# stamp_module.net
KiCad netlist of a schematic drawn in EAGLE
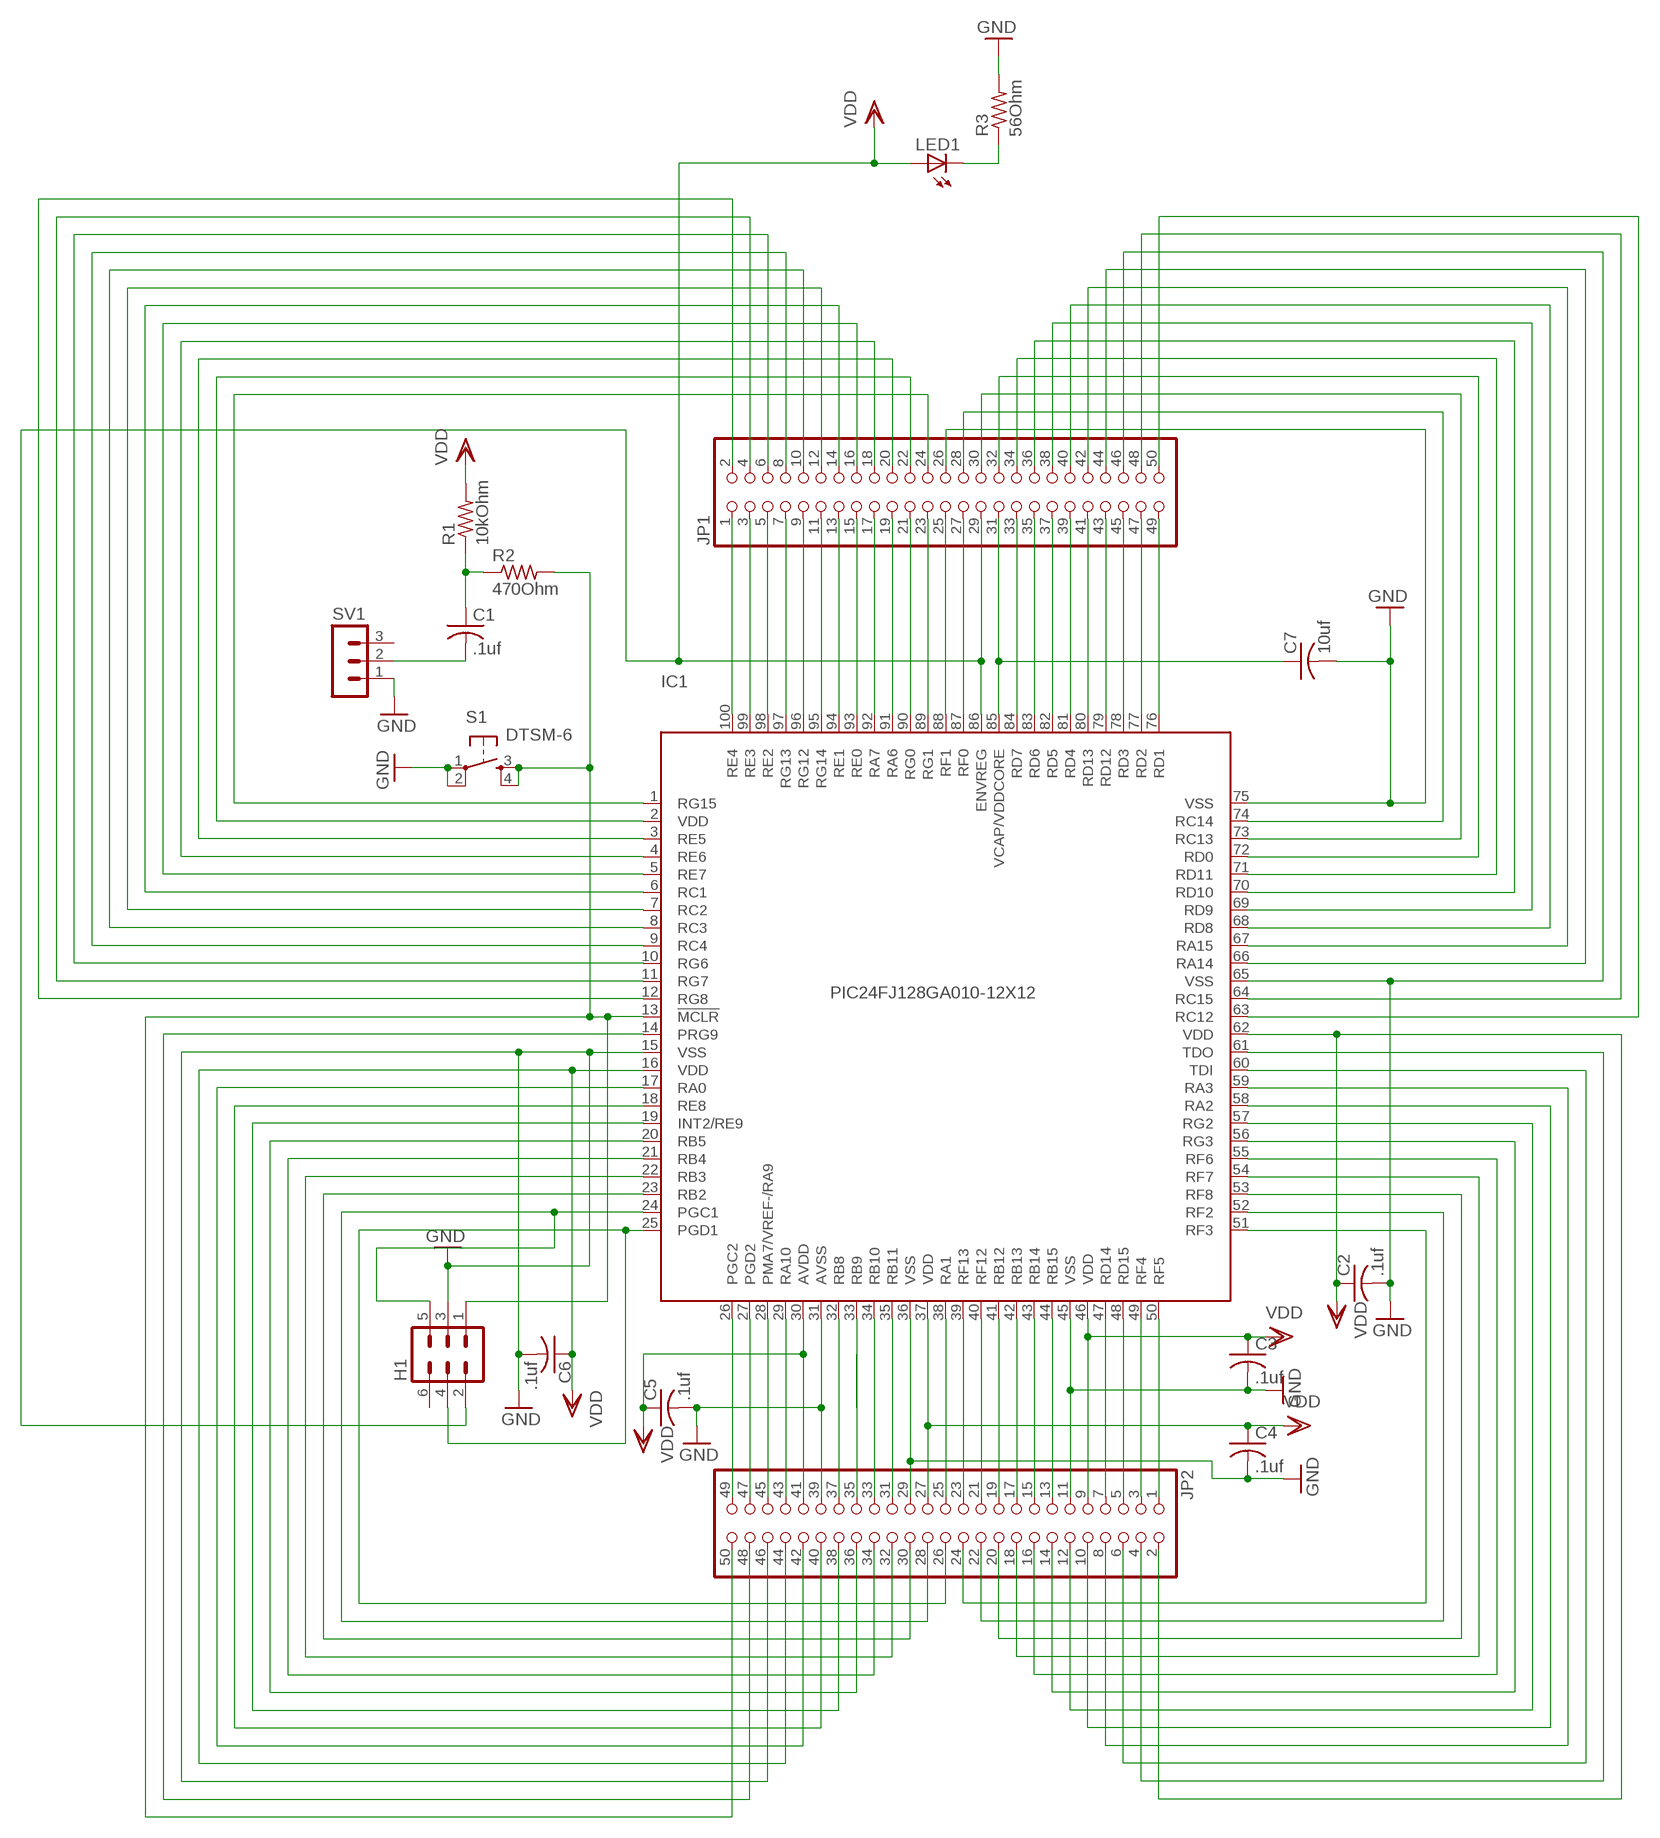
[diagram p0: schematic, sheet 1]

(export (version "E")
  (design (tool "Eeschema 10.0.6"))
  (components
    (comp (ref "C1")
      (value ".1uf")
      (footprint "eagle-import:C1206")
      (libsource (lib "eagle-import") (part "C-USC1206"))
    )
    (comp (ref "C2")
      (value ".1uf")
      (footprint "eagle-import:C1206")
      (libsource (lib "eagle-import") (part "C-USC1206"))
    )
    (comp (ref "C3")
      (value ".1uf")
      (footprint "eagle-import:C1206")
      (libsource (lib "eagle-import") (part "C-USC1206"))
    )
    (comp (ref "C4")
      (value ".1uf")
      (footprint "eagle-import:C1206")
      (libsource (lib "eagle-import") (part "C-USC1206"))
    )
    (comp (ref "C5")
      (value ".1uf")
      (footprint "eagle-import:C1206")
      (libsource (lib "eagle-import") (part "C-USC1206"))
    )
    (comp (ref "C6")
      (value ".1uf")
      (footprint "eagle-import:C1206")
      (libsource (lib "eagle-import") (part "C-USC1206"))
    )
    (comp (ref "C7")
      (value "10uf")
      (footprint "eagle-import:C1206")
      (libsource (lib "eagle-import") (part "C-USC1206"))
    )
    (comp (ref "H1")
      (value "MA03-2")
      (footprint "eagle-import:MA03-2")
      (libsource (lib "eagle-import") (part "MA03-2"))
    )
    (comp (ref "IC1")
      (value "PIC24FJ128GA010-12X12")
      (footprint "eagle-import:SQFP-S-12X12-100")
      (libsource (lib "eagle-import") (part "PIC24FJ128GA010-12X12"))
    )
    (comp (ref "JP1")
      (value "PINHD-2X25")
      (footprint "eagle-import:2X25")
      (libsource (lib "eagle-import") (part "PINHD-2X25"))
    )
    (comp (ref "JP2")
      (value "PINHD-2X25")
      (footprint "eagle-import:2X25")
      (libsource (lib "eagle-import") (part "PINHD-2X25"))
    )
    (comp (ref "LED1")
      (value "LEDCHIPLED_0805")
      (footprint "eagle-import:CHIPLED_0805")
      (libsource (lib "eagle-import") (part "LEDCHIPLED_0805"))
    )
    (comp (ref "R1")
      (value "10kOhm")
      (footprint "eagle-import:R1206")
      (libsource (lib "eagle-import") (part "R-US_R1206"))
    )
    (comp (ref "R2")
      (value "470Ohm")
      (footprint "eagle-import:R1206")
      (libsource (lib "eagle-import") (part "R-US_R1206"))
    )
    (comp (ref "R3")
      (value "56Ohm")
      (footprint "eagle-import:R0805")
      (libsource (lib "eagle-import") (part "R-US_R0805"))
    )
    (comp (ref "S1")
      (value "DTSM-6")
      (footprint "eagle-import:DTSM-6")
      (libsource (lib "eagle-import") (part "DTSM-6"))
    )
    (comp (ref "SV1")
      (value "MA03-1")
      (footprint "eagle-import:MA03-1")
      (libsource (lib "eagle-import") (part "MA03-1"))
    )
  )
  (nets
    (net (code "1") (name "GND") (class "Default")
      (node (ref "C2") (pin "2") (pinfunction "2_2") (pintype "passive"))
      (node (ref "C3") (pin "2") (pinfunction "2_2") (pintype "passive"))
      (node (ref "C4") (pin "2") (pinfunction "2_2") (pintype "passive"))
      (node (ref "C5") (pin "2") (pinfunction "2_2") (pintype "passive"))
      (node (ref "C6") (pin "2") (pinfunction "2_2") (pintype "passive"))
      (node (ref "C7") (pin "2") (pinfunction "2_2") (pintype "passive"))
      (node (ref "H1") (pin "3") (pinfunction "3_3") (pintype "passive"))
      (node (ref "IC1") (pin "15") (pinfunction "VSS_15") (pintype "power_in"))
      (node (ref "IC1") (pin "31") (pinfunction "AVSS_31") (pintype "power_in"))
      (node (ref "IC1") (pin "36") (pinfunction "VSS_36") (pintype "power_in"))
      (node (ref "IC1") (pin "45") (pinfunction "VSS_45") (pintype "power_in"))
      (node (ref "IC1") (pin "65") (pinfunction "VSS_65") (pintype "power_in"))
      (node (ref "IC1") (pin "75") (pinfunction "VSS_75") (pintype "power_in"))
      (node (ref "JP1") (pin "26") (pinfunction "26_26") (pintype "passive"))
      (node (ref "JP1") (pin "46") (pinfunction "46_46") (pintype "passive"))
      (node (ref "JP2") (pin "11") (pinfunction "11_11") (pintype "passive"))
      (node (ref "JP2") (pin "29") (pinfunction "29_29") (pintype "passive"))
      (node (ref "JP2") (pin "39") (pinfunction "39_39") (pintype "passive"))
      (node (ref "JP2") (pin "46") (pinfunction "46_46") (pintype "passive"))
      (node (ref "R3") (pin "2") (pinfunction "2_2") (pintype "passive"))
      (node (ref "S1") (pin "1") (pinfunction "1_1") (pintype "passive"))
      (node (ref "S1") (pin "2") (pinfunction "2_2") (pintype "passive"))
      (node (ref "SV1") (pin "1") (pinfunction "1_1") (pintype "passive"))
    )
    (net (code "2") (name "Net-(C1-Pad1)") (class "Default")
      (node (ref "C1") (pin "1") (pinfunction "1_1") (pintype "passive"))
      (node (ref "R1") (pin "1") (pinfunction "1_1") (pintype "passive"))
      (node (ref "R2") (pin "1") (pinfunction "1_1") (pintype "passive"))
    )
    (net (code "3") (name "Net-(C1-Pad2)") (class "Default")
      (node (ref "C1") (pin "2") (pinfunction "2_2") (pintype "passive"))
      (node (ref "SV1") (pin "2") (pinfunction "2_2") (pintype "passive"))
    )
    (net (code "4") (name "Net-(IC1-INT2{slash}RE9)") (class "Default")
      (node (ref "IC1") (pin "19") (pinfunction "INT2/RE9_19") (pintype "bidirectional"))
      (node (ref "JP2") (pin "38") (pinfunction "38_38") (pintype "passive"))
    )
    (net (code "5") (name "Net-(IC1-PGC1)") (class "Default")
      (node (ref "H1") (pin "5") (pinfunction "5_5") (pintype "passive"))
      (node (ref "IC1") (pin "24") (pinfunction "PGC1_24") (pintype "bidirectional"))
      (node (ref "JP2") (pin "28") (pinfunction "28_28") (pintype "passive"))
    )
    (net (code "6") (name "Net-(IC1-PGC2)") (class "Default")
      (node (ref "IC1") (pin "26") (pinfunction "PGC2_26") (pintype "bidirectional"))
      (node (ref "JP2") (pin "49") (pinfunction "49_49") (pintype "passive"))
    )
    (net (code "7") (name "Net-(IC1-PGD1)") (class "Default")
      (node (ref "H1") (pin "4") (pinfunction "4_4") (pintype "passive"))
      (node (ref "IC1") (pin "25") (pinfunction "PGD1_25") (pintype "bidirectional"))
      (node (ref "JP2") (pin "26") (pinfunction "26_26") (pintype "passive"))
    )
    (net (code "8") (name "Net-(IC1-PGD2)") (class "Default")
      (node (ref "IC1") (pin "27") (pinfunction "PGD2_27") (pintype "bidirectional"))
      (node (ref "JP2") (pin "47") (pinfunction "47_47") (pintype "passive"))
    )
    (net (code "9") (name "Net-(IC1-PMA7{slash}VREF-{slash}RA9)") (class "Default")
      (node (ref "IC1") (pin "28") (pinfunction "PMA7/VREF-/RA9_28") (pintype "bidirectional"))
      (node (ref "JP2") (pin "45") (pinfunction "45_45") (pintype "passive"))
    )
    (net (code "10") (name "Net-(IC1-PRG9)") (class "Default")
      (node (ref "IC1") (pin "14") (pinfunction "PRG9_14") (pintype "bidirectional"))
      (node (ref "JP2") (pin "48") (pinfunction "48_48") (pintype "passive"))
    )
    (net (code "11") (name "Net-(IC1-RA0)") (class "Default")
      (node (ref "IC1") (pin "17") (pinfunction "RA0_17") (pintype "bidirectional"))
      (node (ref "JP2") (pin "42") (pinfunction "42_42") (pintype "passive"))
    )
    (net (code "12") (name "Net-(IC1-RA1)") (class "Default")
      (node (ref "IC1") (pin "38") (pinfunction "RA1_38") (pintype "bidirectional"))
      (node (ref "JP2") (pin "25") (pinfunction "25_25") (pintype "passive"))
    )
    (net (code "13") (name "Net-(IC1-RA2)") (class "Default")
      (node (ref "IC1") (pin "58") (pinfunction "RA2_58") (pintype "bidirectional"))
      (node (ref "JP2") (pin "10") (pinfunction "10_10") (pintype "passive"))
    )
    (net (code "14") (name "Net-(IC1-RA3)") (class "Default")
      (node (ref "IC1") (pin "59") (pinfunction "RA3_59") (pintype "bidirectional"))
      (node (ref "JP2") (pin "8") (pinfunction "8_8") (pintype "passive"))
    )
    (net (code "15") (name "Net-(IC1-RA6)") (class "Default")
      (node (ref "IC1") (pin "91") (pinfunction "RA6_91") (pintype "bidirectional"))
      (node (ref "JP1") (pin "19") (pinfunction "19_19") (pintype "passive"))
    )
    (net (code "16") (name "Net-(IC1-RA7)") (class "Default")
      (node (ref "IC1") (pin "92") (pinfunction "RA7_92") (pintype "bidirectional"))
      (node (ref "JP1") (pin "17") (pinfunction "17_17") (pintype "passive"))
    )
    (net (code "17") (name "Net-(IC1-RA10)") (class "Default")
      (node (ref "IC1") (pin "29") (pinfunction "RA10_29") (pintype "bidirectional"))
      (node (ref "JP2") (pin "43") (pinfunction "43_43") (pintype "passive"))
    )
    (net (code "18") (name "Net-(IC1-RA14)") (class "Default")
      (node (ref "IC1") (pin "66") (pinfunction "RA14_66") (pintype "bidirectional"))
      (node (ref "JP1") (pin "44") (pinfunction "44_44") (pintype "passive"))
    )
    (net (code "19") (name "Net-(IC1-RA15)") (class "Default")
      (node (ref "IC1") (pin "67") (pinfunction "RA15_67") (pintype "bidirectional"))
      (node (ref "JP1") (pin "42") (pinfunction "42_42") (pintype "passive"))
    )
    (net (code "20") (name "Net-(IC1-RB2)") (class "Default")
      (node (ref "IC1") (pin "23") (pinfunction "RB2_23") (pintype "bidirectional"))
      (node (ref "JP2") (pin "30") (pinfunction "30_30") (pintype "passive"))
    )
    (net (code "21") (name "Net-(IC1-RB3)") (class "Default")
      (node (ref "IC1") (pin "22") (pinfunction "RB3_22") (pintype "bidirectional"))
      (node (ref "JP2") (pin "32") (pinfunction "32_32") (pintype "passive"))
    )
    (net (code "22") (name "Net-(IC1-RB4)") (class "Default")
      (node (ref "IC1") (pin "21") (pinfunction "RB4_21") (pintype "bidirectional"))
      (node (ref "JP2") (pin "34") (pinfunction "34_34") (pintype "passive"))
    )
    (net (code "23") (name "Net-(IC1-RB5)") (class "Default")
      (node (ref "IC1") (pin "20") (pinfunction "RB5_20") (pintype "bidirectional"))
      (node (ref "JP2") (pin "36") (pinfunction "36_36") (pintype "passive"))
    )
    (net (code "24") (name "Net-(IC1-RB8)") (class "Default")
      (node (ref "IC1") (pin "32") (pinfunction "RB8_32") (pintype "bidirectional"))
      (node (ref "JP2") (pin "37") (pinfunction "37_37") (pintype "passive"))
    )
    (net (code "25") (name "Net-(IC1-RB9)") (class "Default")
      (node (ref "IC1") (pin "33") (pinfunction "RB9_33") (pintype "bidirectional"))
      (node (ref "JP2") (pin "35") (pinfunction "35_35") (pintype "passive"))
    )
    (net (code "26") (name "Net-(IC1-RB10)") (class "Default")
      (node (ref "IC1") (pin "34") (pinfunction "RB10_34") (pintype "bidirectional"))
      (node (ref "JP2") (pin "33") (pinfunction "33_33") (pintype "passive"))
    )
    (net (code "27") (name "Net-(IC1-RB11)") (class "Default")
      (node (ref "IC1") (pin "35") (pinfunction "RB11_35") (pintype "bidirectional"))
      (node (ref "JP2") (pin "31") (pinfunction "31_31") (pintype "passive"))
    )
    (net (code "28") (name "Net-(IC1-RB12)") (class "Default")
      (node (ref "IC1") (pin "41") (pinfunction "RB12_41") (pintype "bidirectional"))
      (node (ref "JP2") (pin "19") (pinfunction "19_19") (pintype "passive"))
    )
    (net (code "29") (name "Net-(IC1-RB13)") (class "Default")
      (node (ref "IC1") (pin "42") (pinfunction "RB13_42") (pintype "bidirectional"))
      (node (ref "JP2") (pin "17") (pinfunction "17_17") (pintype "passive"))
    )
    (net (code "30") (name "Net-(IC1-RB14)") (class "Default")
      (node (ref "IC1") (pin "43") (pinfunction "RB14_43") (pintype "bidirectional"))
      (node (ref "JP2") (pin "15") (pinfunction "15_15") (pintype "passive"))
    )
    (net (code "31") (name "Net-(IC1-RB15)") (class "Default")
      (node (ref "IC1") (pin "44") (pinfunction "RB15_44") (pintype "bidirectional"))
      (node (ref "JP2") (pin "13") (pinfunction "13_13") (pintype "passive"))
    )
    (net (code "32") (name "Net-(IC1-RC1)") (class "Default")
      (node (ref "IC1") (pin "6") (pinfunction "RC1_6") (pintype "bidirectional"))
      (node (ref "JP1") (pin "14") (pinfunction "14_14") (pintype "passive"))
    )
    (net (code "33") (name "Net-(IC1-RC2)") (class "Default")
      (node (ref "IC1") (pin "7") (pinfunction "RC2_7") (pintype "bidirectional"))
      (node (ref "JP1") (pin "12") (pinfunction "12_12") (pintype "passive"))
    )
    (net (code "34") (name "Net-(IC1-RC3)") (class "Default")
      (node (ref "IC1") (pin "8") (pinfunction "RC3_8") (pintype "bidirectional"))
      (node (ref "JP1") (pin "10") (pinfunction "10_10") (pintype "passive"))
    )
    (net (code "35") (name "Net-(IC1-RC4)") (class "Default")
      (node (ref "IC1") (pin "9") (pinfunction "RC4_9") (pintype "bidirectional"))
      (node (ref "JP1") (pin "8") (pinfunction "8_8") (pintype "passive"))
    )
    (net (code "36") (name "Net-(IC1-RC12)") (class "Default")
      (node (ref "IC1") (pin "63") (pinfunction "RC12_63") (pintype "bidirectional"))
      (node (ref "JP1") (pin "50") (pinfunction "50_50") (pintype "passive"))
    )
    (net (code "37") (name "Net-(IC1-RC13)") (class "Default")
      (node (ref "IC1") (pin "73") (pinfunction "RC13_73") (pintype "bidirectional"))
      (node (ref "JP1") (pin "30") (pinfunction "30_30") (pintype "passive"))
    )
    (net (code "38") (name "Net-(IC1-RC14)") (class "Default")
      (node (ref "IC1") (pin "74") (pinfunction "RC14_74") (pintype "bidirectional"))
      (node (ref "JP1") (pin "28") (pinfunction "28_28") (pintype "passive"))
    )
    (net (code "39") (name "Net-(IC1-RC15)") (class "Default")
      (node (ref "IC1") (pin "64") (pinfunction "RC15_64") (pintype "bidirectional"))
      (node (ref "JP1") (pin "48") (pinfunction "48_48") (pintype "passive"))
    )
    (net (code "40") (name "Net-(IC1-RD0)") (class "Default")
      (node (ref "IC1") (pin "72") (pinfunction "RD0_72") (pintype "bidirectional"))
      (node (ref "JP1") (pin "32") (pinfunction "32_32") (pintype "passive"))
    )
    (net (code "41") (name "Net-(IC1-RD1)") (class "Default")
      (node (ref "IC1") (pin "76") (pinfunction "RD1_76") (pintype "bidirectional"))
      (node (ref "JP1") (pin "49") (pinfunction "49_49") (pintype "passive"))
    )
    (net (code "42") (name "Net-(IC1-RD2)") (class "Default")
      (node (ref "IC1") (pin "77") (pinfunction "RD2_77") (pintype "bidirectional"))
      (node (ref "JP1") (pin "47") (pinfunction "47_47") (pintype "passive"))
    )
    (net (code "43") (name "Net-(IC1-RD3)") (class "Default")
      (node (ref "IC1") (pin "78") (pinfunction "RD3_78") (pintype "bidirectional"))
      (node (ref "JP1") (pin "45") (pinfunction "45_45") (pintype "passive"))
    )
    (net (code "44") (name "Net-(IC1-RD4)") (class "Default")
      (node (ref "IC1") (pin "81") (pinfunction "RD4_81") (pintype "bidirectional"))
      (node (ref "JP1") (pin "39") (pinfunction "39_39") (pintype "passive"))
    )
    (net (code "45") (name "Net-(IC1-RD5)") (class "Default")
      (node (ref "IC1") (pin "82") (pinfunction "RD5_82") (pintype "bidirectional"))
      (node (ref "JP1") (pin "37") (pinfunction "37_37") (pintype "passive"))
    )
    (net (code "46") (name "Net-(IC1-RD6)") (class "Default")
      (node (ref "IC1") (pin "83") (pinfunction "RD6_83") (pintype "bidirectional"))
      (node (ref "JP1") (pin "35") (pinfunction "35_35") (pintype "passive"))
    )
    (net (code "47") (name "Net-(IC1-RD7)") (class "Default")
      (node (ref "IC1") (pin "84") (pinfunction "RD7_84") (pintype "bidirectional"))
      (node (ref "JP1") (pin "33") (pinfunction "33_33") (pintype "passive"))
    )
    (net (code "48") (name "Net-(IC1-RD8)") (class "Default")
      (node (ref "IC1") (pin "68") (pinfunction "RD8_68") (pintype "bidirectional"))
      (node (ref "JP1") (pin "40") (pinfunction "40_40") (pintype "passive"))
    )
    (net (code "49") (name "Net-(IC1-RD9)") (class "Default")
      (node (ref "IC1") (pin "69") (pinfunction "RD9_69") (pintype "bidirectional"))
      (node (ref "JP1") (pin "38") (pinfunction "38_38") (pintype "passive"))
    )
    (net (code "50") (name "Net-(IC1-RD10)") (class "Default")
      (node (ref "IC1") (pin "70") (pinfunction "RD10_70") (pintype "bidirectional"))
      (node (ref "JP1") (pin "36") (pinfunction "36_36") (pintype "passive"))
    )
    (net (code "51") (name "Net-(IC1-RD11)") (class "Default")
      (node (ref "IC1") (pin "71") (pinfunction "RD11_71") (pintype "bidirectional"))
      (node (ref "JP1") (pin "34") (pinfunction "34_34") (pintype "passive"))
    )
    (net (code "52") (name "Net-(IC1-RD12)") (class "Default")
      (node (ref "IC1") (pin "79") (pinfunction "RD12_79") (pintype "bidirectional"))
      (node (ref "JP1") (pin "43") (pinfunction "43_43") (pintype "passive"))
    )
    (net (code "53") (name "Net-(IC1-RD13)") (class "Default")
      (node (ref "IC1") (pin "80") (pinfunction "RD13_80") (pintype "bidirectional"))
      (node (ref "JP1") (pin "41") (pinfunction "41_41") (pintype "passive"))
    )
    (net (code "54") (name "Net-(IC1-RD14)") (class "Default")
      (node (ref "IC1") (pin "47") (pinfunction "RD14_47") (pintype "bidirectional"))
      (node (ref "JP2") (pin "7") (pinfunction "7_7") (pintype "passive"))
    )
    (net (code "55") (name "Net-(IC1-RD15)") (class "Default")
      (node (ref "IC1") (pin "48") (pinfunction "RD15_48") (pintype "bidirectional"))
      (node (ref "JP2") (pin "5") (pinfunction "5_5") (pintype "passive"))
    )
    (net (code "56") (name "Net-(IC1-RE0)") (class "Default")
      (node (ref "IC1") (pin "93") (pinfunction "RE0_93") (pintype "bidirectional"))
      (node (ref "JP1") (pin "15") (pinfunction "15_15") (pintype "passive"))
    )
    (net (code "57") (name "Net-(IC1-RE1)") (class "Default")
      (node (ref "IC1") (pin "94") (pinfunction "RE1_94") (pintype "bidirectional"))
      (node (ref "JP1") (pin "13") (pinfunction "13_13") (pintype "passive"))
    )
    (net (code "58") (name "Net-(IC1-RE2)") (class "Default")
      (node (ref "IC1") (pin "98") (pinfunction "RE2_98") (pintype "bidirectional"))
      (node (ref "JP1") (pin "5") (pinfunction "5_5") (pintype "passive"))
    )
    (net (code "59") (name "Net-(IC1-RE3)") (class "Default")
      (node (ref "IC1") (pin "99") (pinfunction "RE3_99") (pintype "bidirectional"))
      (node (ref "JP1") (pin "3") (pinfunction "3_3") (pintype "passive"))
    )
    (net (code "60") (name "Net-(IC1-RE4)") (class "Default")
      (node (ref "IC1") (pin "100") (pinfunction "RE4_100") (pintype "bidirectional"))
      (node (ref "JP1") (pin "1") (pinfunction "1_1") (pintype "passive"))
    )
    (net (code "61") (name "Net-(IC1-RE5)") (class "Default")
      (node (ref "IC1") (pin "3") (pinfunction "RE5_3") (pintype "bidirectional"))
      (node (ref "JP1") (pin "20") (pinfunction "20_20") (pintype "passive"))
    )
    (net (code "62") (name "Net-(IC1-RE6)") (class "Default")
      (node (ref "IC1") (pin "4") (pinfunction "RE6_4") (pintype "bidirectional"))
      (node (ref "JP1") (pin "18") (pinfunction "18_18") (pintype "passive"))
    )
    (net (code "63") (name "Net-(IC1-RE7)") (class "Default")
      (node (ref "IC1") (pin "5") (pinfunction "RE7_5") (pintype "bidirectional"))
      (node (ref "JP1") (pin "16") (pinfunction "16_16") (pintype "passive"))
    )
    (net (code "64") (name "Net-(IC1-RE8)") (class "Default")
      (node (ref "IC1") (pin "18") (pinfunction "RE8_18") (pintype "bidirectional"))
      (node (ref "JP2") (pin "40") (pinfunction "40_40") (pintype "passive"))
    )
    (net (code "65") (name "Net-(IC1-RF0)") (class "Default")
      (node (ref "IC1") (pin "87") (pinfunction "RF0_87") (pintype "bidirectional"))
      (node (ref "JP1") (pin "27") (pinfunction "27_27") (pintype "passive"))
    )
    (net (code "66") (name "Net-(IC1-RF1)") (class "Default")
      (node (ref "IC1") (pin "88") (pinfunction "RF1_88") (pintype "bidirectional"))
      (node (ref "JP1") (pin "25") (pinfunction "25_25") (pintype "passive"))
    )
    (net (code "67") (name "Net-(IC1-RF2)") (class "Default")
      (node (ref "IC1") (pin "52") (pinfunction "RF2_52") (pintype "bidirectional"))
      (node (ref "JP2") (pin "22") (pinfunction "22_22") (pintype "passive"))
    )
    (net (code "68") (name "Net-(IC1-RF3)") (class "Default")
      (node (ref "IC1") (pin "51") (pinfunction "RF3_51") (pintype "bidirectional"))
      (node (ref "JP2") (pin "24") (pinfunction "24_24") (pintype "passive"))
    )
    (net (code "69") (name "Net-(IC1-RF4)") (class "Default")
      (node (ref "IC1") (pin "49") (pinfunction "RF4_49") (pintype "bidirectional"))
      (node (ref "JP2") (pin "3") (pinfunction "3_3") (pintype "passive"))
    )
    (net (code "70") (name "Net-(IC1-RF5)") (class "Default")
      (node (ref "IC1") (pin "50") (pinfunction "RF5_50") (pintype "bidirectional"))
      (node (ref "JP2") (pin "1") (pinfunction "1_1") (pintype "passive"))
    )
    (net (code "71") (name "Net-(IC1-RF6)") (class "Default")
      (node (ref "IC1") (pin "55") (pinfunction "RF6_55") (pintype "bidirectional"))
      (node (ref "JP2") (pin "16") (pinfunction "16_16") (pintype "passive"))
    )
    (net (code "72") (name "Net-(IC1-RF7)") (class "Default")
      (node (ref "IC1") (pin "54") (pinfunction "RF7_54") (pintype "bidirectional"))
      (node (ref "JP2") (pin "18") (pinfunction "18_18") (pintype "passive"))
    )
    (net (code "73") (name "Net-(IC1-RF8)") (class "Default")
      (node (ref "IC1") (pin "53") (pinfunction "RF8_53") (pintype "bidirectional"))
      (node (ref "JP2") (pin "20") (pinfunction "20_20") (pintype "passive"))
    )
    (net (code "74") (name "Net-(IC1-RF12)") (class "Default")
      (node (ref "IC1") (pin "40") (pinfunction "RF12_40") (pintype "bidirectional"))
      (node (ref "JP2") (pin "21") (pinfunction "21_21") (pintype "passive"))
    )
    (net (code "75") (name "Net-(IC1-RF13)") (class "Default")
      (node (ref "IC1") (pin "39") (pinfunction "RF13_39") (pintype "bidirectional"))
      (node (ref "JP2") (pin "23") (pinfunction "23_23") (pintype "passive"))
    )
    (net (code "76") (name "Net-(IC1-RG0)") (class "Default")
      (node (ref "IC1") (pin "90") (pinfunction "RG0_90") (pintype "bidirectional"))
      (node (ref "JP1") (pin "21") (pinfunction "21_21") (pintype "passive"))
    )
    (net (code "77") (name "Net-(IC1-RG1)") (class "Default")
      (node (ref "IC1") (pin "89") (pinfunction "RG1_89") (pintype "bidirectional"))
      (node (ref "JP1") (pin "23") (pinfunction "23_23") (pintype "passive"))
    )
    (net (code "78") (name "Net-(IC1-RG2)") (class "Default")
      (node (ref "IC1") (pin "57") (pinfunction "RG2_57") (pintype "bidirectional"))
      (node (ref "JP2") (pin "12") (pinfunction "12_12") (pintype "passive"))
    )
    (net (code "79") (name "Net-(IC1-RG3)") (class "Default")
      (node (ref "IC1") (pin "56") (pinfunction "RG3_56") (pintype "bidirectional"))
      (node (ref "JP2") (pin "14") (pinfunction "14_14") (pintype "passive"))
    )
    (net (code "80") (name "Net-(IC1-RG6)") (class "Default")
      (node (ref "IC1") (pin "10") (pinfunction "RG6_10") (pintype "bidirectional"))
      (node (ref "JP1") (pin "6") (pinfunction "6_6") (pintype "passive"))
    )
    (net (code "81") (name "Net-(IC1-RG7)") (class "Default")
      (node (ref "IC1") (pin "11") (pinfunction "RG7_11") (pintype "bidirectional"))
      (node (ref "JP1") (pin "4") (pinfunction "4_4") (pintype "passive"))
    )
    (net (code "82") (name "Net-(IC1-RG8)") (class "Default")
      (node (ref "IC1") (pin "12") (pinfunction "RG8_12") (pintype "bidirectional"))
      (node (ref "JP1") (pin "2") (pinfunction "2_2") (pintype "passive"))
    )
    (net (code "83") (name "Net-(IC1-RG12)") (class "Default")
      (node (ref "IC1") (pin "96") (pinfunction "RG12_96") (pintype "bidirectional"))
      (node (ref "JP1") (pin "9") (pinfunction "9_9") (pintype "passive"))
    )
    (net (code "84") (name "Net-(IC1-RG13)") (class "Default")
      (node (ref "IC1") (pin "97") (pinfunction "RG13_97") (pintype "bidirectional"))
      (node (ref "JP1") (pin "7") (pinfunction "7_7") (pintype "passive"))
    )
    (net (code "85") (name "Net-(IC1-RG14)") (class "Default")
      (node (ref "IC1") (pin "95") (pinfunction "RG14_95") (pintype "bidirectional"))
      (node (ref "JP1") (pin "11") (pinfunction "11_11") (pintype "passive"))
    )
    (net (code "86") (name "Net-(IC1-RG15)") (class "Default")
      (node (ref "IC1") (pin "1") (pinfunction "RG15_1") (pintype "bidirectional"))
      (node (ref "JP1") (pin "24") (pinfunction "24_24") (pintype "passive"))
    )
    (net (code "87") (name "Net-(IC1-TDI)") (class "Default")
      (node (ref "IC1") (pin "60") (pinfunction "TDI_60") (pintype "bidirectional"))
      (node (ref "JP2") (pin "6") (pinfunction "6_6") (pintype "passive"))
    )
    (net (code "88") (name "Net-(IC1-TDO)") (class "Default")
      (node (ref "IC1") (pin "61") (pinfunction "TDO_61") (pintype "bidirectional"))
      (node (ref "JP2") (pin "4") (pinfunction "4_4") (pintype "passive"))
    )
    (net (code "89") (name "Net-(IC1-VCAP{slash}VDDCORE)") (class "Default")
      (node (ref "C7") (pin "1") (pinfunction "1_1") (pintype "passive"))
      (node (ref "IC1") (pin "85") (pinfunction "VCAP/VDDCORE_85") (pintype "bidirectional"))
      (node (ref "JP1") (pin "31") (pinfunction "31_31") (pintype "passive"))
    )
    (net (code "90") (name "Net-(IC1-VDD-Pad2)") (class "Default")
      (node (ref "IC1") (pin "2") (pinfunction "VDD_2") (pintype "power_in"))
      (node (ref "JP1") (pin "22") (pinfunction "22_22") (pintype "passive"))
    )
    (net (code "91") (name "Net-(IC1-~{MCLR})") (class "Default")
      (node (ref "H1") (pin "1") (pinfunction "1_1") (pintype "passive"))
      (node (ref "IC1") (pin "13") (pinfunction "~{MCLR}_13") (pintype "bidirectional"))
      (node (ref "JP2") (pin "50") (pinfunction "50_50") (pintype "passive"))
      (node (ref "R2") (pin "2") (pinfunction "2_2") (pintype "passive"))
      (node (ref "S1") (pin "3") (pinfunction "3_3") (pintype "passive"))
      (node (ref "S1") (pin "4") (pinfunction "4_4") (pintype "passive"))
    )
    (net (code "92") (name "Net-(LED1-PadC)") (class "Default")
      (node (ref "LED1") (pin "C") (pinfunction "C_C") (pintype "passive"))
      (node (ref "R3") (pin "1") (pinfunction "1_1") (pintype "passive"))
    )
    (net (code "93") (name "VDD") (class "Default")
      (node (ref "C2") (pin "1") (pinfunction "1_1") (pintype "passive"))
      (node (ref "C3") (pin "1") (pinfunction "1_1") (pintype "passive"))
      (node (ref "C4") (pin "1") (pinfunction "1_1") (pintype "passive"))
      (node (ref "C5") (pin "1") (pinfunction "1_1") (pintype "passive"))
      (node (ref "C6") (pin "1") (pinfunction "1_1") (pintype "passive"))
      (node (ref "H1") (pin "2") (pinfunction "2_2") (pintype "passive"))
      (node (ref "IC1") (pin "16") (pinfunction "VDD_16") (pintype "power_in"))
      (node (ref "IC1") (pin "30") (pinfunction "AVDD_30") (pintype "power_in"))
      (node (ref "IC1") (pin "37") (pinfunction "VDD_37") (pintype "power_in"))
      (node (ref "IC1") (pin "46") (pinfunction "VDD_46") (pintype "power_in"))
      (node (ref "IC1") (pin "62") (pinfunction "VDD_62") (pintype "power_in"))
      (node (ref "IC1") (pin "86") (pinfunction "ENVREG_86") (pintype "bidirectional"))
      (node (ref "JP1") (pin "29") (pinfunction "29_29") (pintype "passive"))
      (node (ref "JP2") (pin "2") (pinfunction "2_2") (pintype "passive"))
      (node (ref "JP2") (pin "27") (pinfunction "27_27") (pintype "passive"))
      (node (ref "JP2") (pin "41") (pinfunction "41_41") (pintype "passive"))
      (node (ref "JP2") (pin "44") (pinfunction "44_44") (pintype "passive"))
      (node (ref "JP2") (pin "9") (pinfunction "9_9") (pintype "passive"))
      (node (ref "LED1") (pin "A") (pinfunction "A_A") (pintype "passive"))
      (node (ref "R1") (pin "2") (pinfunction "2_2") (pintype "passive"))
    )
    (net (code "94") (name "unconnected-(H1-Pad6)") (class "Default")
      (node (ref "H1") (pin "6") (pinfunction "6_6") (pintype "passive"))
    )
    (net (code "95") (name "unconnected-(SV1-Pad3)") (class "Default")
      (node (ref "SV1") (pin "3") (pinfunction "3_3") (pintype "passive"))
    )
  )
)
